# Sheet1.net
KiCad netlist of a schematic drawn in Altium Designer
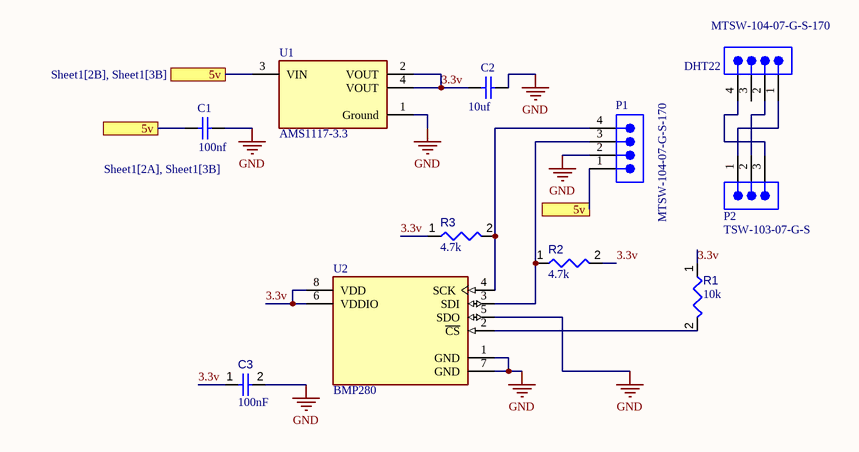
[diagram p0: Sheet1.SchDoc]

(export (version "E")
  (design (tool "Eeschema 10.0.6"))
  (components
    (comp (ref "C1")
      (value "100nf")
      (footprint "CAPC2013X135X50ML15T20")
      (fields (field (name "MANUFACTURER") "Vitramon") (field (name "PART NUMBER") "VJ0805Y104KXATW1BC"))
      (libsource (lib "Altium Content Vault") (part "CAP"))
    )
    (comp (ref "C2")
      (value "10uf")
      (footprint "CAPC2013X140X50ML20T25")
      (fields
        (field (name "PART NUMBER") "08056D106KAT4A")
        (field (name "MANUFACTURER") "AVX Interconnect / Elco")
      )
      (libsource (lib "Altium Content Vault") (part "CAP"))
    )
    (comp (ref "C3")
      (value "100nF")
      (footprint "CAPC2013X95X50LL10T25")
      (description "Chip Capacitor, 100 nF, +/- 10%, 50 V, 0805 (2012 Metric)")
      (fields (field (name "TOLERANCE") "10%") (field (name "Comment") "Capacitor 100 nF +/-10% 50 V 0805"))
      (libsource (lib "Prince Jangir") (part "CAP-NP-2"))
    )
    (comp (ref "DHT22")
      (value "MTSW-104-07-G-S-170")
      (footprint "SMTC-MTSW-104-07-X-S-170")
      (fields (field (name "MANUFACTURER") "Samtec"))
      (libsource (lib "Altium Content Vault") (part "SMTC-MTSW-104-07-X-S-170"))
    )
    (comp (ref "P1")
      (value "MTSW-104-07-G-S-170")
      (footprint "SMTC-MTSW-104-07-X-S-170")
      (fields (field (name "MANUFACTURER") "Samtec"))
      (libsource (lib "Altium Content Vault") (part "SMTC-MTSW-104-07-X-S-170"))
    )
    (comp (ref "P2")
      (value "TSW-103-07-G-S")
      (footprint "SMTC-TSW-103-07-X-S")
      (description "0.025\" SQ Post Header, Through-hole, Vertical, -55 to 125 degC, 2.54 mm Pitch, 3-Pin, Male, RoHS")
      (fields (field (name "MANUFACTURER") "Samtec"))
      (libsource (lib "Altium Content Vault") (part "SMTC-TSW-103-X-X-S-X"))
    )
    (comp (ref "R1")
      (value "10k")
      (footprint "RESC2013X50X35ML15T15")
      (description "Chip Resistor, 10 KOhm, +/- 1%, 125 mW, -55 to 155 degC, 0805 (2012 Metric)")
      (fields (field (name "TOLERANCE") "1%") (field (name "POWER") "125mW"))
      (libsource (lib "Prince Jangir") (part "RES-2"))
    )
    (comp (ref "R2")
      (value "4.7k")
      (footprint "RESC2013X70X40ML20T20")
      (description "Chip Resistor, 4.7 KOhm, +/- 1%, 0.125 W, -55 to 155 degC, 0805 (2012 Metric)")
      (fields (field (name "POWER") "125mW") (field (name "TOLERANCE") "1%"))
      (libsource (lib "Prince Jangir") (part "RES-2"))
    )
    (comp (ref "R3")
      (value "4.7k")
      (footprint "RESC2013X70X40ML20T20")
      (description "Chip Resistor, 4.7 KOhm, +/- 1%, 0.125 W, -55 to 155 degC, 0805 (2012 Metric)")
      (fields (field (name "POWER") "125mW") (field (name "TOLERANCE") "1%"))
      (libsource (lib "Prince Jangir") (part "RES-2"))
    )
    (comp (ref "U1")
      (value "AMS1117-3.3")
      (footprint "FP-AMS1117-IPC_C")
      (description "LDO Voltage Regulators 1A, 3.3V")
      (fields
        (field (name "OCTOPART") "https://octopart.com/ams1117-3.3-advanced+monolithic+systems-25899300")
        (field (name "MANUFACTURER") "Advanced Monolithic Systems")
      )
      (libsource (lib "Altium Content Vault") (part "8bdbb5f8e77002000e30dd2845d0354"))
    )
    (comp (ref "U2")
      (value "BMP280")
      (footprint "FP-BMP280-MFG")
      (description "SENSOR PRESSURE ABS")
      (libsource (lib "Altium Content Vault") (part "69b1aacbb03d82763a43fac02afba64"))
    )
  )
  (nets
    (net (code "1") (name "/3.3v") (class "Default")
      (node (ref "C2") (pin "2") (pinfunction "2_2") (pintype "passive"))
      (node (ref "C3") (pin "1") (pinfunction "1_1") (pintype "passive"))
      (node (ref "R1") (pin "1") (pinfunction "1_1") (pintype "passive"))
      (node (ref "R2") (pin "2") (pinfunction "2_2") (pintype "passive"))
      (node (ref "R3") (pin "1") (pinfunction "1_1") (pintype "passive"))
      (node (ref "U1") (pin "2") (pinfunction "VOUT_2") (pintype "passive"))
      (node (ref "U1") (pin "4") (pinfunction "VOUT_4") (pintype "passive"))
      (node (ref "U2") (pin "6") (pinfunction "VDDIO_6") (pintype "power_in"))
      (node (ref "U2") (pin "8") (pinfunction "VDD_8") (pintype "power_in"))
    )
    (net (code "2") (name "/5v") (class "Default")
      (node (ref "C1") (pin "1") (pinfunction "1_1") (pintype "passive"))
      (node (ref "P1") (pin "1") (pinfunction "1_1") (pintype "passive"))
      (node (ref "U1") (pin "3") (pinfunction "VIN_3") (pintype "power_in"))
    )
    (net (code "3") (name "GND") (class "Default")
      (node (ref "C1") (pin "2") (pinfunction "2_2") (pintype "passive"))
      (node (ref "C2") (pin "1") (pinfunction "1_1") (pintype "passive"))
      (node (ref "C3") (pin "2") (pinfunction "2_2") (pintype "passive"))
      (node (ref "P1") (pin "2") (pinfunction "2_2") (pintype "passive"))
      (node (ref "U1") (pin "1") (pinfunction "Ground_1") (pintype "power_in"))
      (node (ref "U2") (pin "1") (pinfunction "GND_1") (pintype "power_in"))
      (node (ref "U2") (pin "5") (pinfunction "SDO_5") (pintype "bidirectional"))
      (node (ref "U2") (pin "7") (pinfunction "GND_7") (pintype "power_in"))
    )
    (net (code "4") (name "Net-(DHT22-Pad1)") (class "Default")
      (node (ref "DHT22") (pin "1") (pinfunction "1_1") (pintype "passive"))
      (node (ref "P2") (pin "1") (pinfunction "1_1") (pintype "passive"))
    )
    (net (code "5") (name "Net-(DHT22-Pad2)") (class "Default")
      (node (ref "DHT22") (pin "2") (pinfunction "2_2") (pintype "passive"))
      (node (ref "P2") (pin "2") (pinfunction "2_2") (pintype "passive"))
    )
    (net (code "6") (name "Net-(DHT22-Pad4)") (class "Default")
      (node (ref "DHT22") (pin "4") (pinfunction "4_4") (pintype "passive"))
      (node (ref "P2") (pin "3") (pinfunction "3_3") (pintype "passive"))
    )
    (net (code "7") (name "Net-(U2-SCK)") (class "Default")
      (node (ref "P1") (pin "4") (pinfunction "4_4") (pintype "passive"))
      (node (ref "R3") (pin "2") (pinfunction "2_2") (pintype "passive"))
      (node (ref "U2") (pin "4") (pinfunction "SCK_4") (pintype "input"))
    )
    (net (code "8") (name "Net-(U2-SDI)") (class "Default")
      (node (ref "P1") (pin "3") (pinfunction "3_3") (pintype "passive"))
      (node (ref "R2") (pin "1") (pinfunction "1_1") (pintype "passive"))
      (node (ref "U2") (pin "3") (pinfunction "SDI_3") (pintype "bidirectional"))
    )
    (net (code "9") (name "Net-(U2-~{CS})") (class "Default")
      (node (ref "R1") (pin "2") (pinfunction "2_2") (pintype "passive"))
      (node (ref "U2") (pin "2") (pinfunction "~{CS}_2") (pintype "input"))
    )
    (net (code "10") (name "unconnected-(DHT22-Pad3)") (class "Default")
      (node (ref "DHT22") (pin "3") (pinfunction "3_3") (pintype "passive"))
    )
  )
)
